# SolderStation_LCD_v1.net
KiCad netlist of a schematic drawn in EAGLE
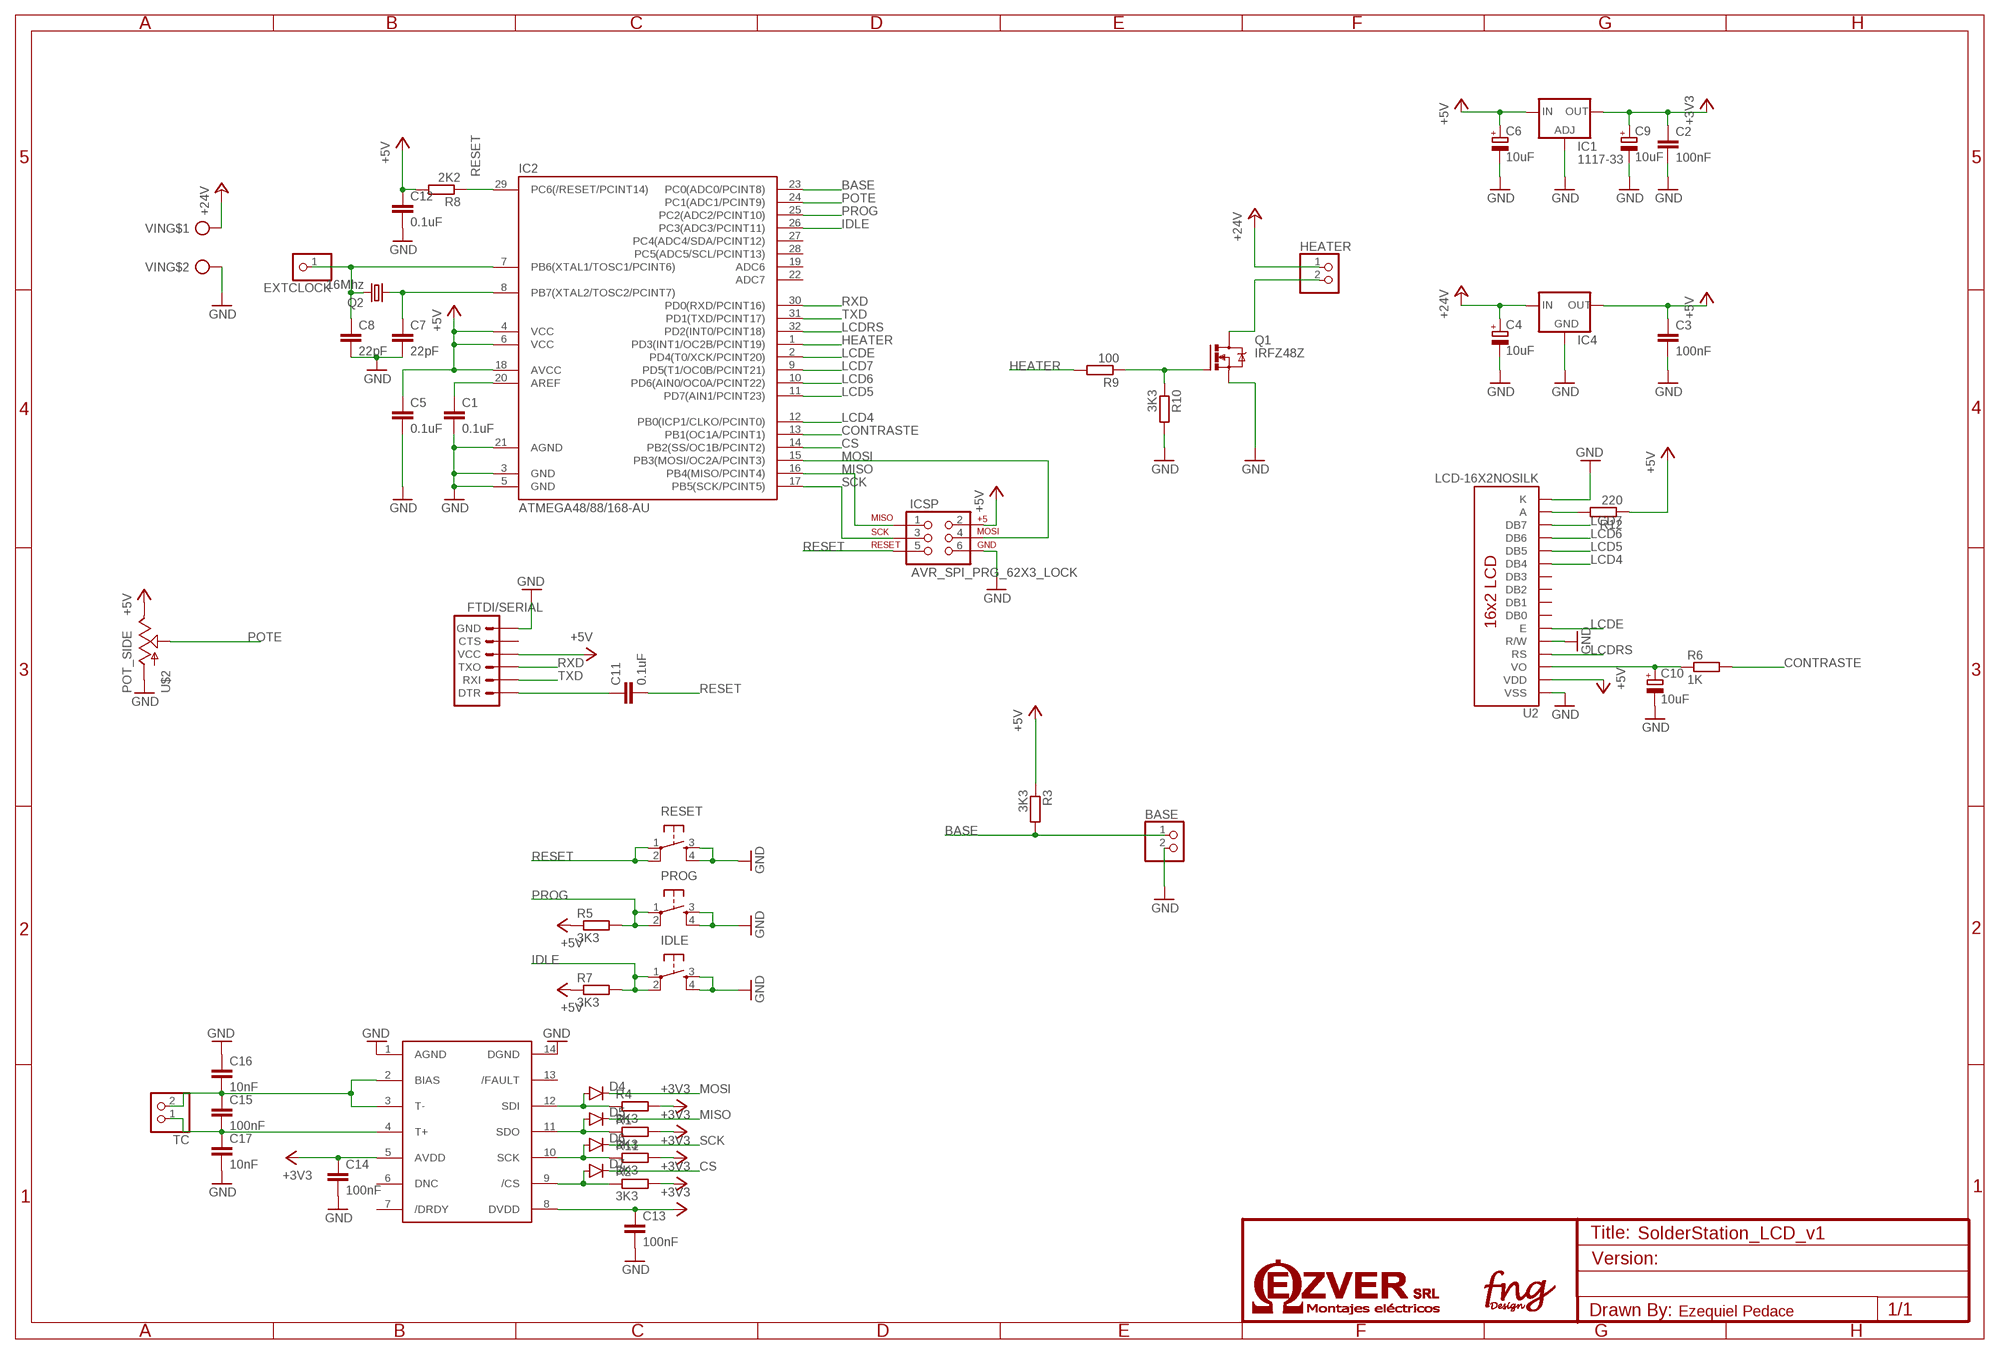
[diagram p0: schematic, sheet 1]

(export (version "E")
  (design (tool "Eeschema 10.0.6"))
  (components
    (comp (ref "BASE")
      (value "PINHD-1X2")
      (footprint "eagle-import:1X02")
      (libsource (lib "eagle-import") (part "PINHD-1X2"))
    )
    (comp (ref "C1")
      (value "0.1uF")
      (footprint "eagle-import:C1206K")
      (libsource (lib "eagle-import") (part "C-EUC1206K"))
    )
    (comp (ref "C2")
      (value "100nF")
      (footprint "eagle-import:C1206K")
      (libsource (lib "eagle-import") (part "C-EUC1206K"))
    )
    (comp (ref "C3")
      (value "100nF")
      (footprint "eagle-import:C1206K")
      (libsource (lib "eagle-import") (part "C-EUC1206K"))
    )
    (comp (ref "C4")
      (value "10uF")
      (footprint "eagle-import:CT3528")
      (libsource (lib "eagle-import") (part "CPOL-EUCT3528"))
    )
    (comp (ref "C5")
      (value "0.1uF")
      (footprint "eagle-import:C1206K")
      (libsource (lib "eagle-import") (part "C-EUC1206K"))
    )
    (comp (ref "C6")
      (value "10uF")
      (footprint "eagle-import:CT3528")
      (libsource (lib "eagle-import") (part "CPOL-EUCT3528"))
    )
    (comp (ref "C7")
      (value "22pF")
      (footprint "eagle-import:C1206K")
      (libsource (lib "eagle-import") (part "C-EUC1206K"))
    )
    (comp (ref "C8")
      (value "22pF")
      (footprint "eagle-import:C1206K")
      (libsource (lib "eagle-import") (part "C-EUC1206K"))
    )
    (comp (ref "C9")
      (value "10uF")
      (footprint "eagle-import:CT3528")
      (libsource (lib "eagle-import") (part "CPOL-EUCT3528"))
    )
    (comp (ref "C10")
      (value "10uF")
      (footprint "eagle-import:CT3528")
      (libsource (lib "eagle-import") (part "CPOL-EUCT3528"))
    )
    (comp (ref "C11")
      (value "0.1uF")
      (footprint "eagle-import:C1206K")
      (libsource (lib "eagle-import") (part "C-EUC1206K"))
    )
    (comp (ref "C12")
      (value "0.1uF")
      (footprint "eagle-import:C1206K")
      (libsource (lib "eagle-import") (part "C-EUC1206K"))
    )
    (comp (ref "C13")
      (value "100nF")
      (footprint "eagle-import:C1206K")
      (libsource (lib "eagle-import") (part "C-EUC1206K"))
    )
    (comp (ref "C14")
      (value "100nF")
      (footprint "eagle-import:C1206K")
      (libsource (lib "eagle-import") (part "C-EUC1206K"))
    )
    (comp (ref "C15")
      (value "100nF")
      (footprint "eagle-import:C1206K")
      (libsource (lib "eagle-import") (part "C-EUC1206K"))
    )
    (comp (ref "C16")
      (value "10nF")
      (footprint "eagle-import:C1206K")
      (libsource (lib "eagle-import") (part "C-EUC1206K"))
    )
    (comp (ref "C17")
      (value "10nF")
      (footprint "eagle-import:C1206K")
      (libsource (lib "eagle-import") (part "C-EUC1206K"))
    )
    (comp (ref "D4")
      (value "DIODESOD123")
      (footprint "eagle-import:SOD-123")
      (libsource (lib "eagle-import") (part "DIODESOD123"))
    )
    (comp (ref "D5")
      (value "DIODESOD123")
      (footprint "eagle-import:SOD-123")
      (libsource (lib "eagle-import") (part "DIODESOD123"))
    )
    (comp (ref "D6")
      (value "DIODESOD123")
      (footprint "eagle-import:SOD-123")
      (libsource (lib "eagle-import") (part "DIODESOD123"))
    )
    (comp (ref "D7")
      (value "DIODESOD123")
      (footprint "eagle-import:SOD-123")
      (libsource (lib "eagle-import") (part "DIODESOD123"))
    )
    (comp (ref "EXTCLOCK")
      (value "PINHD-1X1")
      (footprint "eagle-import:1X01")
      (libsource (lib "eagle-import") (part "PINHD-1X1"))
    )
    (comp (ref "FTDI/SERIAL")
      (value "ARDUINO_SERIAL_PROGRAMLOCK")
      (footprint "eagle-import:1X06_LOCK")
      (libsource (lib "eagle-import") (part "ARDUINO_SERIAL_PROGRAMLOCK"))
    )
    (comp (ref "HEATER")
      (value "PINHD-1X2")
      (footprint "eagle-import:1X02")
      (libsource (lib "eagle-import") (part "PINHD-1X2"))
    )
    (comp (ref "IC1")
      (value "1117-33")
      (footprint "eagle-import:DPACK")
      (libsource (lib "eagle-import") (part "LD117A?DT33TR"))
    )
    (comp (ref "IC2")
      (value "ATMEGA48/88/168-AU")
      (footprint "eagle-import:TQFP32-08")
      (libsource (lib "eagle-import") (part "ATMEGA48/88/168-AU"))
    )
    (comp (ref "IC4")
      (value "78XXL")
      (footprint "eagle-import:78XXL")
      (libsource (lib "eagle-import") (part "78XXL"))
    )
    (comp (ref "ICSP")
      (value "AVR_SPI_PRG_62X3_LOCK")
      (footprint "eagle-import:2X3_LOCK")
      (libsource (lib "eagle-import") (part "AVR_SPI_PRG_62X3_LOCK"))
    )
    (comp (ref "IDLE")
      (value "TAC_SWITCHPTH")
      (footprint "eagle-import:TACTILE-PTH")
      (libsource (lib "eagle-import") (part "TAC_SWITCHPTH"))
    )
    (comp (ref "PROG")
      (value "TAC_SWITCHPTH")
      (footprint "eagle-import:TACTILE-PTH")
      (libsource (lib "eagle-import") (part "TAC_SWITCHPTH"))
    )
    (comp (ref "Q1")
      (value "IRFZ48Z")
      (footprint "eagle-import:TO220BH")
      (libsource (lib "eagle-import") (part "IRFZ48Z"))
    )
    (comp (ref "Q2")
      (value "16Mhz")
      (footprint "eagle-import:HC49U70")
      (libsource (lib "eagle-import") (part "CRYSTALHC49U70"))
    )
    (comp (ref "R1")
      (value "3K3")
      (footprint "eagle-import:M1206")
      (libsource (lib "eagle-import") (part "R-EU_M1206"))
    )
    (comp (ref "R2")
      (value "3K3")
      (footprint "eagle-import:M1206")
      (libsource (lib "eagle-import") (part "R-EU_M1206"))
    )
    (comp (ref "R3")
      (value "3K3")
      (footprint "eagle-import:M1206")
      (libsource (lib "eagle-import") (part "R-EU_M1206"))
    )
    (comp (ref "R4")
      (value "3K3")
      (footprint "eagle-import:M1206")
      (libsource (lib "eagle-import") (part "R-EU_M1206"))
    )
    (comp (ref "R5")
      (value "3K3")
      (footprint "eagle-import:M1206")
      (libsource (lib "eagle-import") (part "R-EU_M1206"))
    )
    (comp (ref "R6")
      (value "1K")
      (footprint "eagle-import:M1206")
      (libsource (lib "eagle-import") (part "R-EU_M1206"))
    )
    (comp (ref "R7")
      (value "3K3")
      (footprint "eagle-import:M1206")
      (libsource (lib "eagle-import") (part "R-EU_M1206"))
    )
    (comp (ref "R8")
      (value "2K2")
      (footprint "eagle-import:M1206")
      (libsource (lib "eagle-import") (part "R-EU_M1206"))
    )
    (comp (ref "R9")
      (value "100")
      (footprint "eagle-import:M1206")
      (libsource (lib "eagle-import") (part "R-EU_M1206"))
    )
    (comp (ref "R10")
      (value "3K3")
      (footprint "eagle-import:M1206")
      (libsource (lib "eagle-import") (part "R-EU_M1206"))
    )
    (comp (ref "R11")
      (value "3K3")
      (footprint "eagle-import:M1206")
      (libsource (lib "eagle-import") (part "R-EU_M1206"))
    )
    (comp (ref "R12")
      (value "220")
      (footprint "eagle-import:M1206")
      (libsource (lib "eagle-import") (part "R-EU_M1206"))
    )
    (comp (ref "RESET")
      (value "TAC_SWITCHPTH")
      (footprint "eagle-import:TACTILE-PTH")
      (libsource (lib "eagle-import") (part "TAC_SWITCHPTH"))
    )
    (comp (ref "TC")
      (value "PINHD-1X2")
      (footprint "eagle-import:1X02")
      (libsource (lib "eagle-import") (part "PINHD-1X2"))
    )
    (comp (ref "TC1")
      (value "MAX31856")
      (footprint "eagle-import:TSSOP-14")
      (libsource (lib "eagle-import") (part "MAX31856"))
    )
    (comp (ref "U$2")
      (value "POT_SIDE")
      (footprint "eagle-import:POT_ALPHA_SIDE")
      (libsource (lib "eagle-import") (part "POT_SIDE"))
    )
    (comp (ref "U2")
      (value "LCD-16X2NOSILK")
      (footprint "eagle-import:LCD-16X2_NOSILK")
      (libsource (lib "eagle-import") (part "LCD-16X2NOSILK"))
    )
    (comp (ref "VIN")
      (value "CON2")
      (footprint "eagle-import:CON2")
      (libsource (lib "eagle-import") (part "CON2"))
    )
  )
  (nets
    (net (code "1") (name "+3V3") (class "Default")
      (node (ref "C13") (pin "1") (pinfunction "1_1") (pintype "passive"))
      (node (ref "C14") (pin "1") (pinfunction "1_1") (pintype "passive"))
      (node (ref "C2") (pin "1") (pinfunction "1_1") (pintype "passive"))
      (node (ref "C9") (pin "+") (pinfunction "+_+") (pintype "passive"))
      (node (ref "IC1") (pin "4") (pinfunction "OUT_4") (pintype "passive"))
      (node (ref "R1") (pin "2") (pinfunction "2_2") (pintype "passive"))
      (node (ref "R11") (pin "2") (pinfunction "2_2") (pintype "passive"))
      (node (ref "R2") (pin "2") (pinfunction "2_2") (pintype "passive"))
      (node (ref "R4") (pin "2") (pinfunction "2_2") (pintype "passive"))
      (node (ref "TC1") (pin "5") (pinfunction "AVDD_5") (pintype "bidirectional"))
      (node (ref "TC1") (pin "8") (pinfunction "DVDD_8") (pintype "bidirectional"))
    )
    (net (code "2") (name "+5V") (class "Default")
      (node (ref "C12") (pin "1") (pinfunction "1_1") (pintype "passive"))
      (node (ref "C3") (pin "1") (pinfunction "1_1") (pintype "passive"))
      (node (ref "C5") (pin "1") (pinfunction "1_1") (pintype "passive"))
      (node (ref "C6") (pin "+") (pinfunction "+_+") (pintype "passive"))
      (node (ref "FTDI/SERIAL") (pin "4") (pinfunction "VCC_4") (pintype "passive"))
      (node (ref "IC1") (pin "3") (pinfunction "IN_3") (pintype "input"))
      (node (ref "IC2") (pin "18") (pinfunction "AVCC_18") (pintype "passive"))
      (node (ref "IC2") (pin "4") (pinfunction "VCC_4") (pintype "power_in"))
      (node (ref "IC2") (pin "6") (pinfunction "VCC_6") (pintype "power_in"))
      (node (ref "IC4") (pin "OUT") (pinfunction "OUT_OUT") (pintype "passive"))
      (node (ref "ICSP") (pin "2") (pinfunction "2_2") (pintype "passive"))
      (node (ref "R12") (pin "1") (pinfunction "1_1") (pintype "passive"))
      (node (ref "R3") (pin "1") (pinfunction "1_1") (pintype "passive"))
      (node (ref "R5") (pin "1") (pinfunction "1_1") (pintype "passive"))
      (node (ref "R7") (pin "1") (pinfunction "1_1") (pintype "passive"))
      (node (ref "R8") (pin "2") (pinfunction "2_2") (pintype "passive"))
      (node (ref "U$2") (pin "3") (pinfunction "E_3") (pintype "passive"))
      (node (ref "U2") (pin "2") (pinfunction "VDD_2") (pintype "power_in"))
    )
    (net (code "3") (name "+24V") (class "Default")
      (node (ref "C4") (pin "+") (pinfunction "+_+") (pintype "passive"))
      (node (ref "HEATER") (pin "1") (pinfunction "1_1") (pintype "passive"))
      (node (ref "IC4") (pin "IN") (pinfunction "IN_IN") (pintype "input"))
      (node (ref "VIN") (pin "1") (pinfunction "KL_1") (pintype "passive"))
    )
    (net (code "4") (name "/BASE") (class "Default")
      (node (ref "BASE") (pin "1") (pinfunction "1_1") (pintype "passive"))
      (node (ref "IC2") (pin "23") (pinfunction "PC0(ADC0/PCINT8)_23") (pintype "bidirectional"))
      (node (ref "R3") (pin "2") (pinfunction "2_2") (pintype "passive"))
    )
    (net (code "5") (name "/CONTRASTE") (class "Default")
      (node (ref "IC2") (pin "13") (pinfunction "PB1(OC1A/PCINT1)_13") (pintype "bidirectional"))
      (node (ref "R6") (pin "2") (pinfunction "2_2") (pintype "passive"))
    )
    (net (code "6") (name "/CS") (class "Default")
      (node (ref "D7") (pin "C") (pinfunction "C_C") (pintype "passive"))
      (node (ref "IC2") (pin "14") (pinfunction "PB2(SS/OC1B/PCINT2)_14") (pintype "bidirectional"))
    )
    (net (code "7") (name "/HEATER") (class "Default")
      (node (ref "IC2") (pin "1") (pinfunction "PD3(INT1/OC2B/PCINT19)_1") (pintype "bidirectional"))
      (node (ref "R9") (pin "2") (pinfunction "2_2") (pintype "passive"))
    )
    (net (code "8") (name "/IDLE") (class "Default")
      (node (ref "IC2") (pin "26") (pinfunction "PC3(ADC3/PCINT11)_26") (pintype "bidirectional"))
      (node (ref "IDLE") (pin "1") (pinfunction "1_1") (pintype "passive"))
      (node (ref "IDLE") (pin "2") (pinfunction "2_2") (pintype "passive"))
      (node (ref "R7") (pin "2") (pinfunction "2_2") (pintype "passive"))
    )
    (net (code "9") (name "/LCD4") (class "Default")
      (node (ref "IC2") (pin "12") (pinfunction "PB0(ICP1/CLKO/PCINT0)_12") (pintype "bidirectional"))
      (node (ref "U2") (pin "11") (pinfunction "DB4_11") (pintype "bidirectional"))
    )
    (net (code "10") (name "/LCD5") (class "Default")
      (node (ref "IC2") (pin "11") (pinfunction "PD7(AIN1/PCINT23)_11") (pintype "bidirectional"))
      (node (ref "U2") (pin "12") (pinfunction "DB5_12") (pintype "bidirectional"))
    )
    (net (code "11") (name "/LCD6") (class "Default")
      (node (ref "IC2") (pin "10") (pinfunction "PD6(AIN0/OC0A/PCINT22)_10") (pintype "bidirectional"))
      (node (ref "U2") (pin "13") (pinfunction "DB6_13") (pintype "bidirectional"))
    )
    (net (code "12") (name "/LCD7") (class "Default")
      (node (ref "IC2") (pin "9") (pinfunction "PD5(T1/OC0B/PCINT21)_9") (pintype "bidirectional"))
      (node (ref "U2") (pin "14") (pinfunction "DB7_14") (pintype "bidirectional"))
    )
    (net (code "13") (name "/LCDE") (class "Default")
      (node (ref "IC2") (pin "2") (pinfunction "PD4(T0/XCK/PCINT20)_2") (pintype "bidirectional"))
      (node (ref "U2") (pin "6") (pinfunction "E_6") (pintype "input"))
    )
    (net (code "14") (name "/LCDRS") (class "Default")
      (node (ref "IC2") (pin "32") (pinfunction "PD2(INT0/PCINT18)_32") (pintype "bidirectional"))
      (node (ref "U2") (pin "4") (pinfunction "RS_4") (pintype "input"))
    )
    (net (code "15") (name "/MISO") (class "Default")
      (node (ref "D5") (pin "C") (pinfunction "C_C") (pintype "passive"))
      (node (ref "IC2") (pin "16") (pinfunction "PB4(MISO/PCINT4)_16") (pintype "bidirectional"))
      (node (ref "ICSP") (pin "1") (pinfunction "1_1") (pintype "passive"))
    )
    (net (code "16") (name "/MOSI") (class "Default")
      (node (ref "D4") (pin "C") (pinfunction "C_C") (pintype "passive"))
      (node (ref "IC2") (pin "15") (pinfunction "PB3(MOSI/OC2A/PCINT3)_15") (pintype "bidirectional"))
      (node (ref "ICSP") (pin "4") (pinfunction "4_4") (pintype "passive"))
    )
    (net (code "17") (name "/POTE") (class "Default")
      (node (ref "IC2") (pin "24") (pinfunction "PC1(ADC1/PCINT9)_24") (pintype "bidirectional"))
      (node (ref "U$2") (pin "2") (pinfunction "S_2") (pintype "passive"))
    )
    (net (code "18") (name "/PROG") (class "Default")
      (node (ref "IC2") (pin "25") (pinfunction "PC2(ADC2/PCINT10)_25") (pintype "bidirectional"))
      (node (ref "PROG") (pin "1") (pinfunction "1_1") (pintype "passive"))
      (node (ref "PROG") (pin "2") (pinfunction "2_2") (pintype "passive"))
      (node (ref "R5") (pin "2") (pinfunction "2_2") (pintype "passive"))
    )
    (net (code "19") (name "/RESET") (class "Default")
      (node (ref "C11") (pin "2") (pinfunction "2_2") (pintype "passive"))
      (node (ref "IC2") (pin "29") (pinfunction "PC6(/RESET/PCINT14)_29") (pintype "bidirectional"))
      (node (ref "ICSP") (pin "5") (pinfunction "5_5") (pintype "passive"))
      (node (ref "R8") (pin "1") (pinfunction "1_1") (pintype "passive"))
      (node (ref "RESET") (pin "1") (pinfunction "1_1") (pintype "passive"))
      (node (ref "RESET") (pin "2") (pinfunction "2_2") (pintype "passive"))
    )
    (net (code "20") (name "/RXD") (class "Default")
      (node (ref "FTDI/SERIAL") (pin "3") (pinfunction "TXO_3") (pintype "passive"))
      (node (ref "IC2") (pin "30") (pinfunction "PD0(RXD/PCINT16)_30") (pintype "bidirectional"))
    )
    (net (code "21") (name "/SCK") (class "Default")
      (node (ref "D6") (pin "C") (pinfunction "C_C") (pintype "passive"))
      (node (ref "IC2") (pin "17") (pinfunction "PB5(SCK/PCINT5)_17") (pintype "bidirectional"))
      (node (ref "ICSP") (pin "3") (pinfunction "3_3") (pintype "passive"))
    )
    (net (code "22") (name "/TXD") (class "Default")
      (node (ref "FTDI/SERIAL") (pin "2") (pinfunction "RXI_2") (pintype "passive"))
      (node (ref "IC2") (pin "31") (pinfunction "PD1(TXD/PCINT17)_31") (pintype "bidirectional"))
    )
    (net (code "23") (name "GND") (class "Default")
      (node (ref "BASE") (pin "2") (pinfunction "2_2") (pintype "passive"))
      (node (ref "C1") (pin "2") (pinfunction "2_2") (pintype "passive"))
      (node (ref "C10") (pin "-") (pinfunction "-_-") (pintype "passive"))
      (node (ref "C12") (pin "2") (pinfunction "2_2") (pintype "passive"))
      (node (ref "C13") (pin "2") (pinfunction "2_2") (pintype "passive"))
      (node (ref "C14") (pin "2") (pinfunction "2_2") (pintype "passive"))
      (node (ref "C16") (pin "1") (pinfunction "1_1") (pintype "passive"))
      (node (ref "C17") (pin "2") (pinfunction "2_2") (pintype "passive"))
      (node (ref "C2") (pin "2") (pinfunction "2_2") (pintype "passive"))
      (node (ref "C3") (pin "2") (pinfunction "2_2") (pintype "passive"))
      (node (ref "C4") (pin "-") (pinfunction "-_-") (pintype "passive"))
      (node (ref "C5") (pin "2") (pinfunction "2_2") (pintype "passive"))
      (node (ref "C6") (pin "-") (pinfunction "-_-") (pintype "passive"))
      (node (ref "C7") (pin "2") (pinfunction "2_2") (pintype "passive"))
      (node (ref "C8") (pin "2") (pinfunction "2_2") (pintype "passive"))
      (node (ref "C9") (pin "-") (pinfunction "-_-") (pintype "passive"))
      (node (ref "FTDI/SERIAL") (pin "6") (pinfunction "GND_6") (pintype "passive"))
      (node (ref "IC1") (pin "1") (pinfunction "ADJ_1") (pintype "input"))
      (node (ref "IC2") (pin "21") (pinfunction "AGND_21") (pintype "power_in"))
      (node (ref "IC2") (pin "3") (pinfunction "GND_3") (pintype "power_in"))
      (node (ref "IC2") (pin "5") (pinfunction "GND_5") (pintype "power_in"))
      (node (ref "IC4") (pin "GND") (pinfunction "GND_GND") (pintype "input"))
      (node (ref "ICSP") (pin "6") (pinfunction "6_6") (pintype "passive"))
      (node (ref "IDLE") (pin "3") (pinfunction "3_3") (pintype "passive"))
      (node (ref "IDLE") (pin "4") (pinfunction "4_4") (pintype "passive"))
      (node (ref "PROG") (pin "3") (pinfunction "3_3") (pintype "passive"))
      (node (ref "PROG") (pin "4") (pinfunction "4_4") (pintype "passive"))
      (node (ref "Q1") (pin "S") (pinfunction "S_S") (pintype "passive"))
      (node (ref "R10") (pin "2") (pinfunction "2_2") (pintype "passive"))
      (node (ref "RESET") (pin "3") (pinfunction "3_3") (pintype "passive"))
      (node (ref "RESET") (pin "4") (pinfunction "4_4") (pintype "passive"))
      (node (ref "TC1") (pin "1") (pinfunction "AGND_1") (pintype "bidirectional"))
      (node (ref "TC1") (pin "14") (pinfunction "DGND_14") (pintype "bidirectional"))
      (node (ref "U$2") (pin "1") (pinfunction "A_1") (pintype "passive"))
      (node (ref "U2") (pin "1") (pinfunction "VSS_1") (pintype "power_in"))
      (node (ref "U2") (pin "16") (pinfunction "K_16") (pintype "power_in"))
      (node (ref "U2") (pin "5") (pinfunction "R/W_5") (pintype "input"))
      (node (ref "VIN") (pin "2") (pinfunction "KL_2") (pintype "passive"))
    )
    (net (code "24") (name "Net-(FTDI/SERIAL-DTR)") (class "Default")
      (node (ref "C11") (pin "1") (pinfunction "1_1") (pintype "passive"))
      (node (ref "FTDI/SERIAL") (pin "1") (pinfunction "DTR_1") (pintype "passive"))
    )
    (net (code "25") (name "Net-(HEATER-Pad2)") (class "Default")
      (node (ref "HEATER") (pin "2") (pinfunction "2_2") (pintype "passive"))
      (node (ref "Q1") (pin "D") (pinfunction "D_D") (pintype "passive"))
    )
    (net (code "26") (name "Net-(IC2-AREF)") (class "Default")
      (node (ref "C1") (pin "1") (pinfunction "1_1") (pintype "passive"))
      (node (ref "IC2") (pin "20") (pinfunction "AREF_20") (pintype "passive"))
    )
    (net (code "27") (name "Net-(IC2-PB6(XTAL1{slash}TOSC1{slash}PCINT6))") (class "Default")
      (node (ref "C8") (pin "1") (pinfunction "1_1") (pintype "passive"))
      (node (ref "EXTCLOCK") (pin "1") (pinfunction "1_1") (pintype "passive"))
      (node (ref "IC2") (pin "7") (pinfunction "PB6(XTAL1/TOSC1/PCINT6)_7") (pintype "bidirectional"))
      (node (ref "Q2") (pin "2") (pinfunction "2_2") (pintype "passive"))
    )
    (net (code "28") (name "Net-(IC2-PB7(XTAL2{slash}TOSC2{slash}PCINT7))") (class "Default")
      (node (ref "C7") (pin "1") (pinfunction "1_1") (pintype "passive"))
      (node (ref "IC2") (pin "8") (pinfunction "PB7(XTAL2/TOSC2/PCINT7)_8") (pintype "bidirectional"))
      (node (ref "Q2") (pin "1") (pinfunction "1_1") (pintype "passive"))
    )
    (net (code "29") (name "Net-(Q1-PadG)") (class "Default")
      (node (ref "Q1") (pin "G") (pinfunction "G_G") (pintype "passive"))
      (node (ref "R10") (pin "1") (pinfunction "1_1") (pintype "passive"))
      (node (ref "R9") (pin "1") (pinfunction "1_1") (pintype "passive"))
    )
    (net (code "30") (name "Net-(TC1-BIAS)") (class "Default")
      (node (ref "C15") (pin "1") (pinfunction "1_1") (pintype "passive"))
      (node (ref "C16") (pin "2") (pinfunction "2_2") (pintype "passive"))
      (node (ref "TC") (pin "2") (pinfunction "2_2") (pintype "passive"))
      (node (ref "TC1") (pin "2") (pinfunction "BIAS_2") (pintype "bidirectional"))
      (node (ref "TC1") (pin "3") (pinfunction "T-_3") (pintype "bidirectional"))
    )
    (net (code "31") (name "Net-(TC1-SCK)") (class "Default")
      (node (ref "D6") (pin "A") (pinfunction "A_A") (pintype "passive"))
      (node (ref "R11") (pin "1") (pinfunction "1_1") (pintype "passive"))
      (node (ref "TC1") (pin "10") (pinfunction "SCK_10") (pintype "bidirectional"))
    )
    (net (code "32") (name "Net-(TC1-SDI)") (class "Default")
      (node (ref "D4") (pin "A") (pinfunction "A_A") (pintype "passive"))
      (node (ref "R4") (pin "1") (pinfunction "1_1") (pintype "passive"))
      (node (ref "TC1") (pin "12") (pinfunction "SDI_12") (pintype "bidirectional"))
    )
    (net (code "33") (name "Net-(TC1-SDO)") (class "Default")
      (node (ref "D5") (pin "A") (pinfunction "A_A") (pintype "passive"))
      (node (ref "R1") (pin "1") (pinfunction "1_1") (pintype "passive"))
      (node (ref "TC1") (pin "11") (pinfunction "SDO_11") (pintype "bidirectional"))
    )
    (net (code "34") (name "Net-(TC1-T+)") (class "Default")
      (node (ref "C15") (pin "2") (pinfunction "2_2") (pintype "passive"))
      (node (ref "C17") (pin "1") (pinfunction "1_1") (pintype "passive"))
      (node (ref "TC") (pin "1") (pinfunction "1_1") (pintype "passive"))
      (node (ref "TC1") (pin "4") (pinfunction "T+_4") (pintype "bidirectional"))
    )
    (net (code "35") (name "Net-(TC1-{slash}CS)") (class "Default")
      (node (ref "D7") (pin "A") (pinfunction "A_A") (pintype "passive"))
      (node (ref "R2") (pin "1") (pinfunction "1_1") (pintype "passive"))
      (node (ref "TC1") (pin "9") (pinfunction "/CS_9") (pintype "bidirectional"))
    )
    (net (code "36") (name "Net-(U2-A)") (class "Default")
      (node (ref "R12") (pin "2") (pinfunction "2_2") (pintype "passive"))
      (node (ref "U2") (pin "15") (pinfunction "A_15") (pintype "power_in"))
    )
    (net (code "37") (name "Net-(U2-VO)") (class "Default")
      (node (ref "C10") (pin "+") (pinfunction "+_+") (pintype "passive"))
      (node (ref "R6") (pin "1") (pinfunction "1_1") (pintype "passive"))
      (node (ref "U2") (pin "3") (pinfunction "VO_3") (pintype "bidirectional"))
    )
    (net (code "38") (name "unconnected-(FTDI/SERIAL-CTS-Pad5)") (class "Default")
      (node (ref "FTDI/SERIAL") (pin "5") (pinfunction "CTS_5") (pintype "passive"))
    )
    (net (code "39") (name "unconnected-(IC2-ADC6-Pad19)") (class "Default")
      (node (ref "IC2") (pin "19") (pinfunction "ADC6_19") (pintype "passive"))
    )
    (net (code "40") (name "unconnected-(IC2-ADC7-Pad22)") (class "Default")
      (node (ref "IC2") (pin "22") (pinfunction "ADC7_22") (pintype "passive"))
    )
    (net (code "41") (name "unconnected-(IC2-PC4(ADC4{slash}SDA{slash}PCINT12)-Pad27)") (class "Default")
      (node (ref "IC2") (pin "27") (pinfunction "PC4(ADC4/SDA/PCINT12)_27") (pintype "bidirectional"))
    )
    (net (code "42") (name "unconnected-(IC2-PC5(ADC5{slash}SCL{slash}PCINT13)-Pad28)") (class "Default")
      (node (ref "IC2") (pin "28") (pinfunction "PC5(ADC5/SCL/PCINT13)_28") (pintype "bidirectional"))
    )
    (net (code "43") (name "unconnected-(TC1-DNC-Pad6)") (class "Default")
      (node (ref "TC1") (pin "6") (pinfunction "DNC_6") (pintype "bidirectional"))
    )
    (net (code "44") (name "unconnected-(TC1-{slash}DRDY-Pad7)") (class "Default")
      (node (ref "TC1") (pin "7") (pinfunction "/DRDY_7") (pintype "bidirectional"))
    )
    (net (code "45") (name "unconnected-(TC1-{slash}FAULT-Pad13)") (class "Default")
      (node (ref "TC1") (pin "13") (pinfunction "/FAULT_13") (pintype "bidirectional"))
    )
    (net (code "46") (name "unconnected-(U2-DB0-Pad7)") (class "Default")
      (node (ref "U2") (pin "7") (pinfunction "DB0_7") (pintype "bidirectional"))
    )
    (net (code "47") (name "unconnected-(U2-DB1-Pad8)") (class "Default")
      (node (ref "U2") (pin "8") (pinfunction "DB1_8") (pintype "bidirectional"))
    )
    (net (code "48") (name "unconnected-(U2-DB2-Pad9)") (class "Default")
      (node (ref "U2") (pin "9") (pinfunction "DB2_9") (pintype "bidirectional"))
    )
    (net (code "49") (name "unconnected-(U2-DB3-Pad10)") (class "Default")
      (node (ref "U2") (pin "10") (pinfunction "DB3_10") (pintype "bidirectional"))
    )
  )
)
